# Rain_Collector_Outside_v2.net
KiCad netlist of a schematic drawn in EAGLE
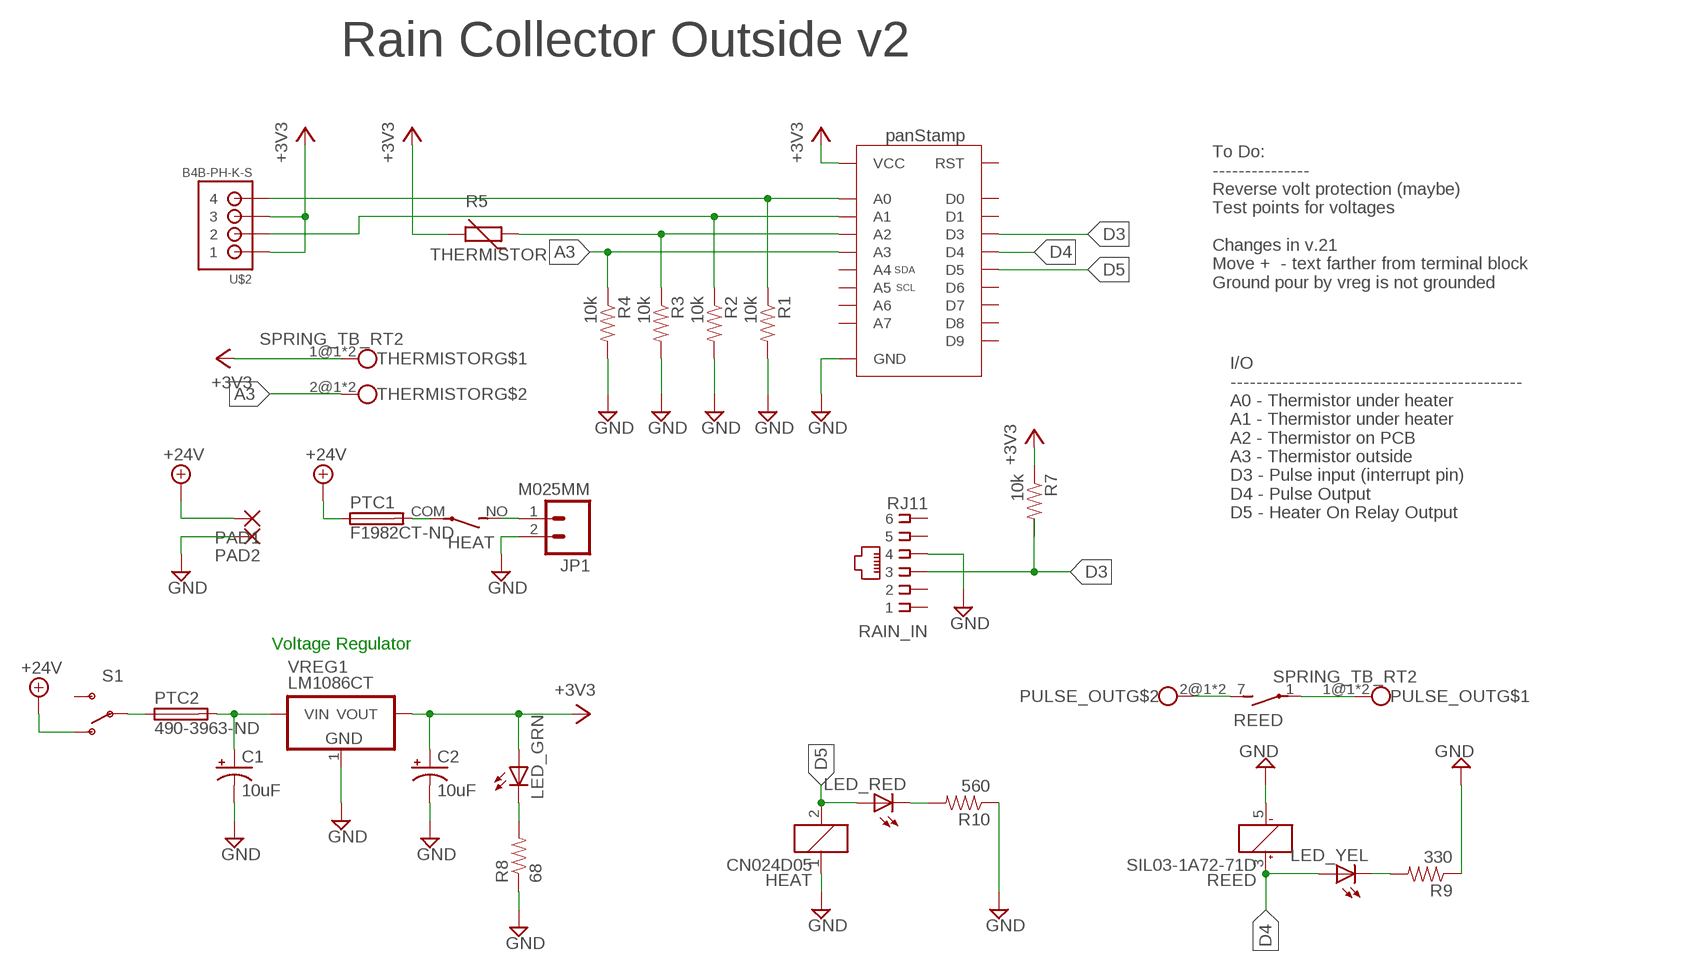
[diagram p0: schematic, sheet 1]

(export (version "E")
  (design (tool "Eeschema 10.0.6"))
  (components
    (comp (ref "C1")
      (value "10uF")
      (footprint "eagle-import:CPOL-RADIAL-10UF-25V")
      (fields (field (name "PARTNO") "478-6062-ND"))
      (libsource (lib "eagle-import") (part "CAP_POLPTH2"))
    )
    (comp (ref "C2")
      (value "10uF")
      (footprint "eagle-import:CPOL-RADIAL-10UF-25V")
      (fields (field (name "PARTNO") "478-6062-ND"))
      (libsource (lib "eagle-import") (part "CAP_POLPTH2"))
    )
    (comp (ref "HEAT")
      (value "CN024D05")
      (footprint "eagle-import:APF30212A")
      (fields (field (name "PARTNO") "CC1742-ND"))
      (libsource (lib "eagle-import") (part "APF30212A"))
    )
    (comp (ref "JP1")
      (value "M025MM")
      (footprint "eagle-import:SCREWTERMINAL-5MM-2")
      (fields (field (name "PARTNO") "Sparkfun PRT-08432"))
      (libsource (lib "eagle-import") (part "M025MM"))
    )
    (comp (ref "LED_GRN")
      (value "LED3MM")
      (footprint "eagle-import:LED3MM")
      (libsource (lib "eagle-import") (part "LED3MM"))
    )
    (comp (ref "LED_RED")
      (value "LED3MM")
      (footprint "eagle-import:LED3MM")
      (libsource (lib "eagle-import") (part "LED3MM"))
    )
    (comp (ref "LED_YEL")
      (value "LED3MM")
      (footprint "eagle-import:LED3MM")
      (libsource (lib "eagle-import") (part "LED3MM"))
    )
    (comp (ref "PAD1")
      (value "3,17/1,3")
      (footprint "eagle-import:3,17_1,3")
      (libsource (lib "eagle-import") (part "3,17/1,3"))
    )
    (comp (ref "PAD2")
      (value "3,17/1,3")
      (footprint "eagle-import:3,17_1,3")
      (libsource (lib "eagle-import") (part "3,17/1,3"))
    )
    (comp (ref "PANSTAMP")
      (value "PANSTAMPNO_TEXT")
      (footprint "eagle-import:PANSTAMP_NOTEXT")
      (libsource (lib "eagle-import") (part "PANSTAMPNO_TEXT"))
    )
    (comp (ref "PTC1")
      (value "F1982CT-ND")
      (footprint "eagle-import:TE5")
      (libsource (lib "eagle-import") (part "TE5"))
    )
    (comp (ref "PTC2")
      (value "490-3963-ND")
      (footprint "eagle-import:TE5")
      (libsource (lib "eagle-import") (part "TE5"))
    )
    (comp (ref "PULSE_OUT")
      (value "SPRING_TB_RT2")
      (footprint "eagle-import:SPRING_TB_RT2")
      (fields (field (name "PARTNO") "Sprakfun PRT-08073"))
      (libsource (lib "eagle-import") (part "SPRING_TB_RT2"))
    )
    (comp (ref "R1")
      (value "10k")
      (footprint "eagle-import:AXIAL-0.3")
      (fields (field (name "PARTNO") "RNF18FTD10K0CT-ND"))
      (libsource (lib "eagle-import") (part "RESISTORAXIAL-0.3"))
    )
    (comp (ref "R2")
      (value "10k")
      (footprint "eagle-import:AXIAL-0.3")
      (fields (field (name "PARTNO") "RNF18FTD10K0CT-ND"))
      (libsource (lib "eagle-import") (part "RESISTORAXIAL-0.3"))
    )
    (comp (ref "R3")
      (value "10k")
      (footprint "eagle-import:AXIAL-0.3")
      (fields (field (name "PARTNO") "RNF18FTD10K0CT-ND"))
      (libsource (lib "eagle-import") (part "RESISTORAXIAL-0.3"))
    )
    (comp (ref "R4")
      (value "10k")
      (footprint "eagle-import:AXIAL-0.3")
      (fields (field (name "PARTNO") "RNF18FTD10K0CT-ND"))
      (libsource (lib "eagle-import") (part "RESISTORAXIAL-0.3"))
    )
    (comp (ref "R5")
      (value "THERMISTOR")
      (footprint "eagle-import:RS-2,5")
      (fields (field (name "PARTNO") "BC2301-ND"))
      (libsource (lib "eagle-import") (part "THERMISTOR-2,5"))
    )
    (comp (ref "R7")
      (value "10k")
      (footprint "eagle-import:AXIAL-0.3")
      (fields (field (name "PARTNO") "RNF18FTD10K0CT-ND"))
      (libsource (lib "eagle-import") (part "RESISTORAXIAL-0.3"))
    )
    (comp (ref "R8")
      (value "68")
      (footprint "eagle-import:AXIAL-0.3")
      (fields (field (name "PARTNO") "CF18JT68R0CT-ND"))
      (libsource (lib "eagle-import") (part "RESISTORAXIAL-0.3"))
    )
    (comp (ref "R9")
      (value "330")
      (footprint "eagle-import:AXIAL-0.3")
      (fields (field (name "PARTNO") "CF18JT330RCT-ND"))
      (libsource (lib "eagle-import") (part "RESISTORAXIAL-0.3"))
    )
    (comp (ref "R10")
      (value "560")
      (footprint "eagle-import:AXIAL-0.3")
      (fields (field (name "PARTNO") "CF18JT560RCT-ND"))
      (libsource (lib "eagle-import") (part "RESISTORAXIAL-0.3"))
    )
    (comp (ref "RAIN_IN")
      (value "RJ11")
      (footprint "eagle-import:RJ11-NO_SHIELD")
      (fields (field (name "PARTNO") "A31406-ND"))
      (libsource (lib "eagle-import") (part "RJ11-2X"))
    )
    (comp (ref "REED")
      (value "SIL03-1A72-71D")
      (footprint "eagle-import:REED")
      (fields (field (name "PARTNO") "374-1322-ND"))
      (libsource (lib "eagle-import") (part "REED"))
    )
    (comp (ref "S1")
      (value "SWITCH-SPDTPTH")
      (footprint "eagle-import:SWITCH-SPDT")
      (fields (field (name "PARTNO") "EG1903-ND"))
      (libsource (lib "eagle-import") (part "SWITCH-SPDTPTH"))
    )
    (comp (ref "THERMISTOR")
      (value "SPRING_TB_RT2")
      (footprint "eagle-import:SPRING_TB_RT2")
      (fields (field (name "PARTNO") "Sparkfun PRT-08073"))
      (libsource (lib "eagle-import") (part "SPRING_TB_RT2"))
    )
    (comp (ref "U$2")
      (value "B4B-PH-K-S")
      (footprint "eagle-import:JST_B4B-PH_HEADER")
      (fields (field (name "PARTNO") "455-1706-ND"))
      (libsource (lib "eagle-import") (part "JST-PH_4-PIN_HEADER"))
    )
    (comp (ref "VREG1")
      (value "LM1086CT")
      (footprint "eagle-import:TO-220V")
      (libsource (lib "eagle-import") (part "VREG_3PINS-TO-220V"))
    )
  )
  (nets
    (net (code "1") (name "+3V3") (class "Default")
      (node (ref "C2") (pin "1") (pinfunction "+_1") (pintype "passive"))
      (node (ref "LED_GRN") (pin "A") (pinfunction "A_A") (pintype "passive"))
      (node (ref "PANSTAMP") (pin "VCC") (pinfunction "VCC_VCC") (pintype "power_in"))
      (node (ref "R5") (pin "2") (pinfunction "2_2") (pintype "passive"))
      (node (ref "R7") (pin "P$1") (pinfunction "1_P$1") (pintype "passive"))
      (node (ref "THERMISTOR") (pin "1@1") (pinfunction "1_1@1") (pintype "passive"))
      (node (ref "THERMISTOR") (pin "1@2") (pinfunction "1_1@2") (pintype "passive"))
      (node (ref "U$2") (pin "P1") (pinfunction "1_P1") (pintype "bidirectional"))
      (node (ref "U$2") (pin "P3") (pinfunction "3_P3") (pintype "bidirectional"))
      (node (ref "VREG1") (pin "2") (pinfunction "VOUT_2") (pintype "bidirectional"))
    )
    (net (code "2") (name "+24V") (class "Default")
      (node (ref "PAD1") (pin "1") (pinfunction "P_1") (pintype "passive"))
      (node (ref "PTC1") (pin "1") (pinfunction "1_1") (pintype "passive"))
      (node (ref "S1") (pin "1") (pinfunction "O_1") (pintype "passive"))
    )
    (net (code "3") (name "A3") (class "Default")
      (node (ref "PANSTAMP") (pin "A3") (pinfunction "A3_A3") (pintype "bidirectional"))
      (node (ref "R4") (pin "P$1") (pinfunction "1_P$1") (pintype "passive"))
      (node (ref "THERMISTOR") (pin "2@1") (pinfunction "1_2@1") (pintype "passive"))
      (node (ref "THERMISTOR") (pin "2@2") (pinfunction "1_2@2") (pintype "passive"))
    )
    (net (code "4") (name "D3") (class "Default")
      (node (ref "PANSTAMP") (pin "D3") (pinfunction "D3_D3") (pintype "bidirectional"))
      (node (ref "R7") (pin "P$2") (pinfunction "2_P$2") (pintype "passive"))
      (node (ref "RAIN_IN") (pin "3") (pinfunction "3_3") (pintype "passive"))
    )
    (net (code "5") (name "D4") (class "Default")
      (node (ref "LED_YEL") (pin "A") (pinfunction "A_A") (pintype "passive"))
      (node (ref "PANSTAMP") (pin "D4") (pinfunction "D4_D4") (pintype "bidirectional"))
      (node (ref "REED") (pin "3") (pinfunction "+_3") (pintype "passive"))
    )
    (net (code "6") (name "D5") (class "Default")
      (node (ref "HEAT") (pin "2") (pinfunction "2_2") (pintype "passive"))
      (node (ref "LED_RED") (pin "A") (pinfunction "A_A") (pintype "passive"))
      (node (ref "PANSTAMP") (pin "D5") (pinfunction "D5_D5") (pintype "bidirectional"))
    )
    (net (code "7") (name "GND") (class "Default")
      (node (ref "C1") (pin "2") (pinfunction "-_2") (pintype "passive"))
      (node (ref "C2") (pin "2") (pinfunction "-_2") (pintype "passive"))
      (node (ref "HEAT") (pin "1") (pinfunction "1_1") (pintype "passive"))
      (node (ref "JP1") (pin "2") (pinfunction "2_2") (pintype "passive"))
      (node (ref "PAD2") (pin "1") (pinfunction "P_1") (pintype "passive"))
      (node (ref "PANSTAMP") (pin "GND$1") (pinfunction "GND_GND$1") (pintype "power_in"))
      (node (ref "PANSTAMP") (pin "GND$15") (pinfunction "GND_GND$15") (pintype "power_in"))
      (node (ref "PANSTAMP") (pin "GND$23") (pinfunction "GND_GND$23") (pintype "power_in"))
      (node (ref "PANSTAMP") (pin "GND$24") (pinfunction "GND_GND$24") (pintype "power_in"))
      (node (ref "PANSTAMP") (pin "GND$7") (pinfunction "GND_GND$7") (pintype "power_in"))
      (node (ref "R1") (pin "P$2") (pinfunction "2_P$2") (pintype "passive"))
      (node (ref "R10") (pin "P$1") (pinfunction "1_P$1") (pintype "passive"))
      (node (ref "R2") (pin "P$2") (pinfunction "2_P$2") (pintype "passive"))
      (node (ref "R3") (pin "P$2") (pinfunction "2_P$2") (pintype "passive"))
      (node (ref "R4") (pin "P$2") (pinfunction "2_P$2") (pintype "passive"))
      (node (ref "R8") (pin "P$1") (pinfunction "1_P$1") (pintype "passive"))
      (node (ref "R9") (pin "P$1") (pinfunction "1_P$1") (pintype "passive"))
      (node (ref "RAIN_IN") (pin "4") (pinfunction "4_4") (pintype "passive"))
      (node (ref "REED") (pin "5") (pinfunction "-_5") (pintype "passive"))
      (node (ref "VREG1") (pin "1") (pinfunction "GND_1") (pintype "bidirectional"))
    )
    (net (code "8") (name "Net-(C1-+)") (class "Default")
      (node (ref "C1") (pin "1") (pinfunction "+_1") (pintype "passive"))
      (node (ref "PTC2") (pin "2") (pinfunction "2_2") (pintype "passive"))
      (node (ref "VREG1") (pin "3") (pinfunction "VIN_3") (pintype "bidirectional"))
    )
    (net (code "9") (name "Net-(HEATB-P)") (class "Default")
      (node (ref "HEAT") (pin "COM") (pinfunction "P_COM") (pintype "passive"))
      (node (ref "PTC1") (pin "2") (pinfunction "2_2") (pintype "passive"))
    )
    (net (code "10") (name "Net-(HEATB-S)") (class "Default")
      (node (ref "HEAT") (pin "NO") (pinfunction "S_NO") (pintype "passive"))
      (node (ref "JP1") (pin "1") (pinfunction "1_1") (pintype "passive"))
    )
    (net (code "11") (name "Net-(LED_GRN-C)") (class "Default")
      (node (ref "LED_GRN") (pin "K") (pinfunction "C_K") (pintype "passive"))
      (node (ref "R8") (pin "P$2") (pinfunction "2_P$2") (pintype "passive"))
    )
    (net (code "12") (name "Net-(LED_RED-C)") (class "Default")
      (node (ref "LED_RED") (pin "K") (pinfunction "C_K") (pintype "passive"))
      (node (ref "R10") (pin "P$2") (pinfunction "2_P$2") (pintype "passive"))
    )
    (net (code "13") (name "Net-(LED_YEL-C)") (class "Default")
      (node (ref "LED_YEL") (pin "K") (pinfunction "C_K") (pintype "passive"))
      (node (ref "R9") (pin "P$2") (pinfunction "2_P$2") (pintype "passive"))
    )
    (net (code "14") (name "Net-(R1-1)") (class "Default")
      (node (ref "PANSTAMP") (pin "A0") (pinfunction "A0_A0") (pintype "bidirectional"))
      (node (ref "R1") (pin "P$1") (pinfunction "1_P$1") (pintype "passive"))
      (node (ref "U$2") (pin "P4") (pinfunction "4_P4") (pintype "bidirectional"))
    )
    (net (code "15") (name "Net-(R2-1)") (class "Default")
      (node (ref "PANSTAMP") (pin "A1") (pinfunction "A1_A1") (pintype "bidirectional"))
      (node (ref "R2") (pin "P$1") (pinfunction "1_P$1") (pintype "passive"))
      (node (ref "U$2") (pin "P2") (pinfunction "2_P2") (pintype "bidirectional"))
    )
    (net (code "16") (name "Net-(R3-1)") (class "Default")
      (node (ref "PANSTAMP") (pin "A2") (pinfunction "A2_A2") (pintype "bidirectional"))
      (node (ref "R3") (pin "P$1") (pinfunction "1_P$1") (pintype "passive"))
      (node (ref "R5") (pin "1") (pinfunction "1_1") (pintype "passive"))
    )
    (net (code "17") (name "Net-(REEDB-P)") (class "Default")
      (node (ref "PULSE_OUT") (pin "1@1") (pinfunction "1_1@1") (pintype "passive"))
      (node (ref "PULSE_OUT") (pin "1@2") (pinfunction "1_1@2") (pintype "passive"))
      (node (ref "REED") (pin "1") (pinfunction "P_1") (pintype "passive"))
    )
    (net (code "18") (name "Net-(REEDB-S)") (class "Default")
      (node (ref "PULSE_OUT") (pin "2@1") (pinfunction "1_2@1") (pintype "passive"))
      (node (ref "PULSE_OUT") (pin "2@2") (pinfunction "1_2@2") (pintype "passive"))
      (node (ref "REED") (pin "7") (pinfunction "S_7") (pintype "passive"))
    )
    (net (code "19") (name "Net-(S1-P)") (class "Default")
      (node (ref "PTC2") (pin "1") (pinfunction "1_1") (pintype "passive"))
      (node (ref "S1") (pin "2") (pinfunction "P_2") (pintype "passive"))
    )
    (net (code "20") (name "unconnected-(PANSTAMP-PadA4)") (class "Default")
      (node (ref "PANSTAMP") (pin "A4") (pinfunction "A4_A4") (pintype "bidirectional"))
    )
    (net (code "21") (name "unconnected-(PANSTAMP-PadA5)") (class "Default")
      (node (ref "PANSTAMP") (pin "A5") (pinfunction "A5_A5") (pintype "bidirectional"))
    )
    (net (code "22") (name "unconnected-(PANSTAMP-PadA6)") (class "Default")
      (node (ref "PANSTAMP") (pin "A6") (pinfunction "A6_A6") (pintype "bidirectional"))
    )
    (net (code "23") (name "unconnected-(PANSTAMP-PadA7)") (class "Default")
      (node (ref "PANSTAMP") (pin "A7") (pinfunction "A7_A7") (pintype "bidirectional"))
    )
    (net (code "24") (name "unconnected-(PANSTAMP-PadD0)") (class "Default")
      (node (ref "PANSTAMP") (pin "D0") (pinfunction "D0_D0") (pintype "bidirectional"))
    )
    (net (code "25") (name "unconnected-(PANSTAMP-PadD1)") (class "Default")
      (node (ref "PANSTAMP") (pin "D1") (pinfunction "D1_D1") (pintype "bidirectional"))
    )
    (net (code "26") (name "unconnected-(PANSTAMP-PadD6)") (class "Default")
      (node (ref "PANSTAMP") (pin "D6") (pinfunction "D6_D6") (pintype "bidirectional"))
    )
    (net (code "27") (name "unconnected-(PANSTAMP-PadD7)") (class "Default")
      (node (ref "PANSTAMP") (pin "D7") (pinfunction "D7_D7") (pintype "bidirectional"))
    )
    (net (code "28") (name "unconnected-(PANSTAMP-PadD8)") (class "Default")
      (node (ref "PANSTAMP") (pin "D8") (pinfunction "D8_D8") (pintype "bidirectional"))
    )
    (net (code "29") (name "unconnected-(PANSTAMP-PadD9)") (class "Default")
      (node (ref "PANSTAMP") (pin "D9") (pinfunction "D9_D9") (pintype "bidirectional"))
    )
    (net (code "30") (name "unconnected-(PANSTAMP-RST-PadRESET)") (class "Default")
      (node (ref "PANSTAMP") (pin "RESET") (pinfunction "RST_RESET") (pintype "bidirectional"))
    )
    (net (code "31") (name "unconnected-(RAIN_IN-Pad1)") (class "Default")
      (node (ref "RAIN_IN") (pin "1") (pinfunction "1_1") (pintype "passive"))
    )
    (net (code "32") (name "unconnected-(RAIN_IN-Pad2)") (class "Default")
      (node (ref "RAIN_IN") (pin "2") (pinfunction "2_2") (pintype "passive"))
    )
    (net (code "33") (name "unconnected-(RAIN_IN-Pad5)") (class "Default")
      (node (ref "RAIN_IN") (pin "5") (pinfunction "5_5") (pintype "passive"))
    )
    (net (code "34") (name "unconnected-(RAIN_IN-Pad6)") (class "Default")
      (node (ref "RAIN_IN") (pin "6") (pinfunction "6_6") (pintype "passive"))
    )
    (net (code "35") (name "unconnected-(S1-S-Pad3)") (class "Default")
      (node (ref "S1") (pin "3") (pinfunction "S_3") (pintype "passive"))
    )
  )
)
